# 4_12.net
KiCad netlist of a schematic drawn in EasyEDA
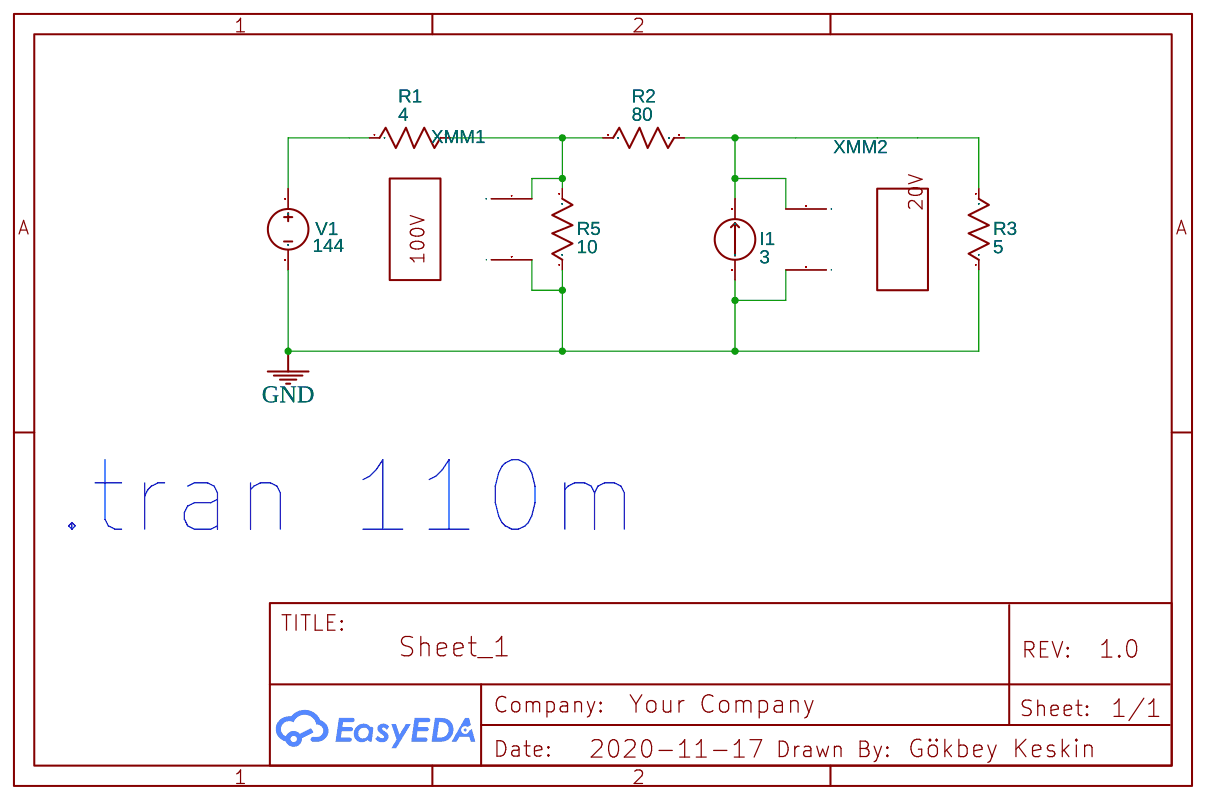
[diagram p0: schematic sheet]

(export (version "E")
  (design (tool "Eeschema 10.0.6"))
  (components
    (comp (ref "I1") (value "3") (libsource (lib "") (part "IDC")))
    (comp (ref "R1") (value "4") (libsource (lib "") (part "Resistor_US")))
    (comp (ref "R2") (value "80") (libsource (lib "") (part "Resistor_US")))
    (comp (ref "R3") (value "5") (libsource (lib "") (part "Resistor_US_1")))
    (comp (ref "R5") (value "10") (libsource (lib "") (part "Resistor_US_1")))
    (comp (ref "V1") (value "144") (libsource (lib "") (part "VDC")))
    (comp (ref "XMM1") (value "Multimeter") (libsource (lib "") (part "MULTIMETER")))
    (comp (ref "XMM2") (value "Multimeter") (libsource (lib "") (part "MULTIMETER_1")))
  )
  (nets
    (net (code "1") (name "GND") (class "Default")
      (node (ref "I1") (pin "1") (pinfunction "1_1") (pintype "unspecified"))
      (node (ref "R3") (pin "1") (pinfunction "1_1") (pintype "unspecified"))
      (node (ref "R5") (pin "1") (pinfunction "1_1") (pintype "unspecified"))
      (node (ref "V1") (pin "2") (pinfunction "2_2") (pintype "unspecified"))
      (node (ref "XMM1") (pin "2") (pinfunction "I_2") (pintype "unspecified"))
      (node (ref "XMM2") (pin "2") (pinfunction "I_2") (pintype "unspecified"))
    )
    (net (code "2") (name "Net-(R1-Pad1)") (class "Default")
      (node (ref "R1") (pin "1") (pinfunction "1_1") (pintype "unspecified"))
      (node (ref "V1") (pin "1") (pinfunction "1_1") (pintype "unspecified"))
    )
    (net (code "3") (name "Net-(XMM1-+)") (class "Default")
      (node (ref "R1") (pin "2") (pinfunction "2_2") (pintype "unspecified"))
      (node (ref "R2") (pin "1") (pinfunction "1_1") (pintype "unspecified"))
      (node (ref "R5") (pin "2") (pinfunction "2_2") (pintype "unspecified"))
      (node (ref "XMM1") (pin "1") (pinfunction "+_1") (pintype "unspecified"))
    )
    (net (code "4") (name "Net-(XMM2-+)") (class "Default")
      (node (ref "I1") (pin "2") (pinfunction "2_2") (pintype "unspecified"))
      (node (ref "R2") (pin "2") (pinfunction "2_2") (pintype "unspecified"))
      (node (ref "R3") (pin "2") (pinfunction "2_2") (pintype "unspecified"))
      (node (ref "XMM2") (pin "1") (pinfunction "+_1") (pintype "unspecified"))
    )
  )
)
